# LB_BIT_o9_BARGRAPH-v02_rev1.net
KiCad netlist of a schematic drawn in EAGLE
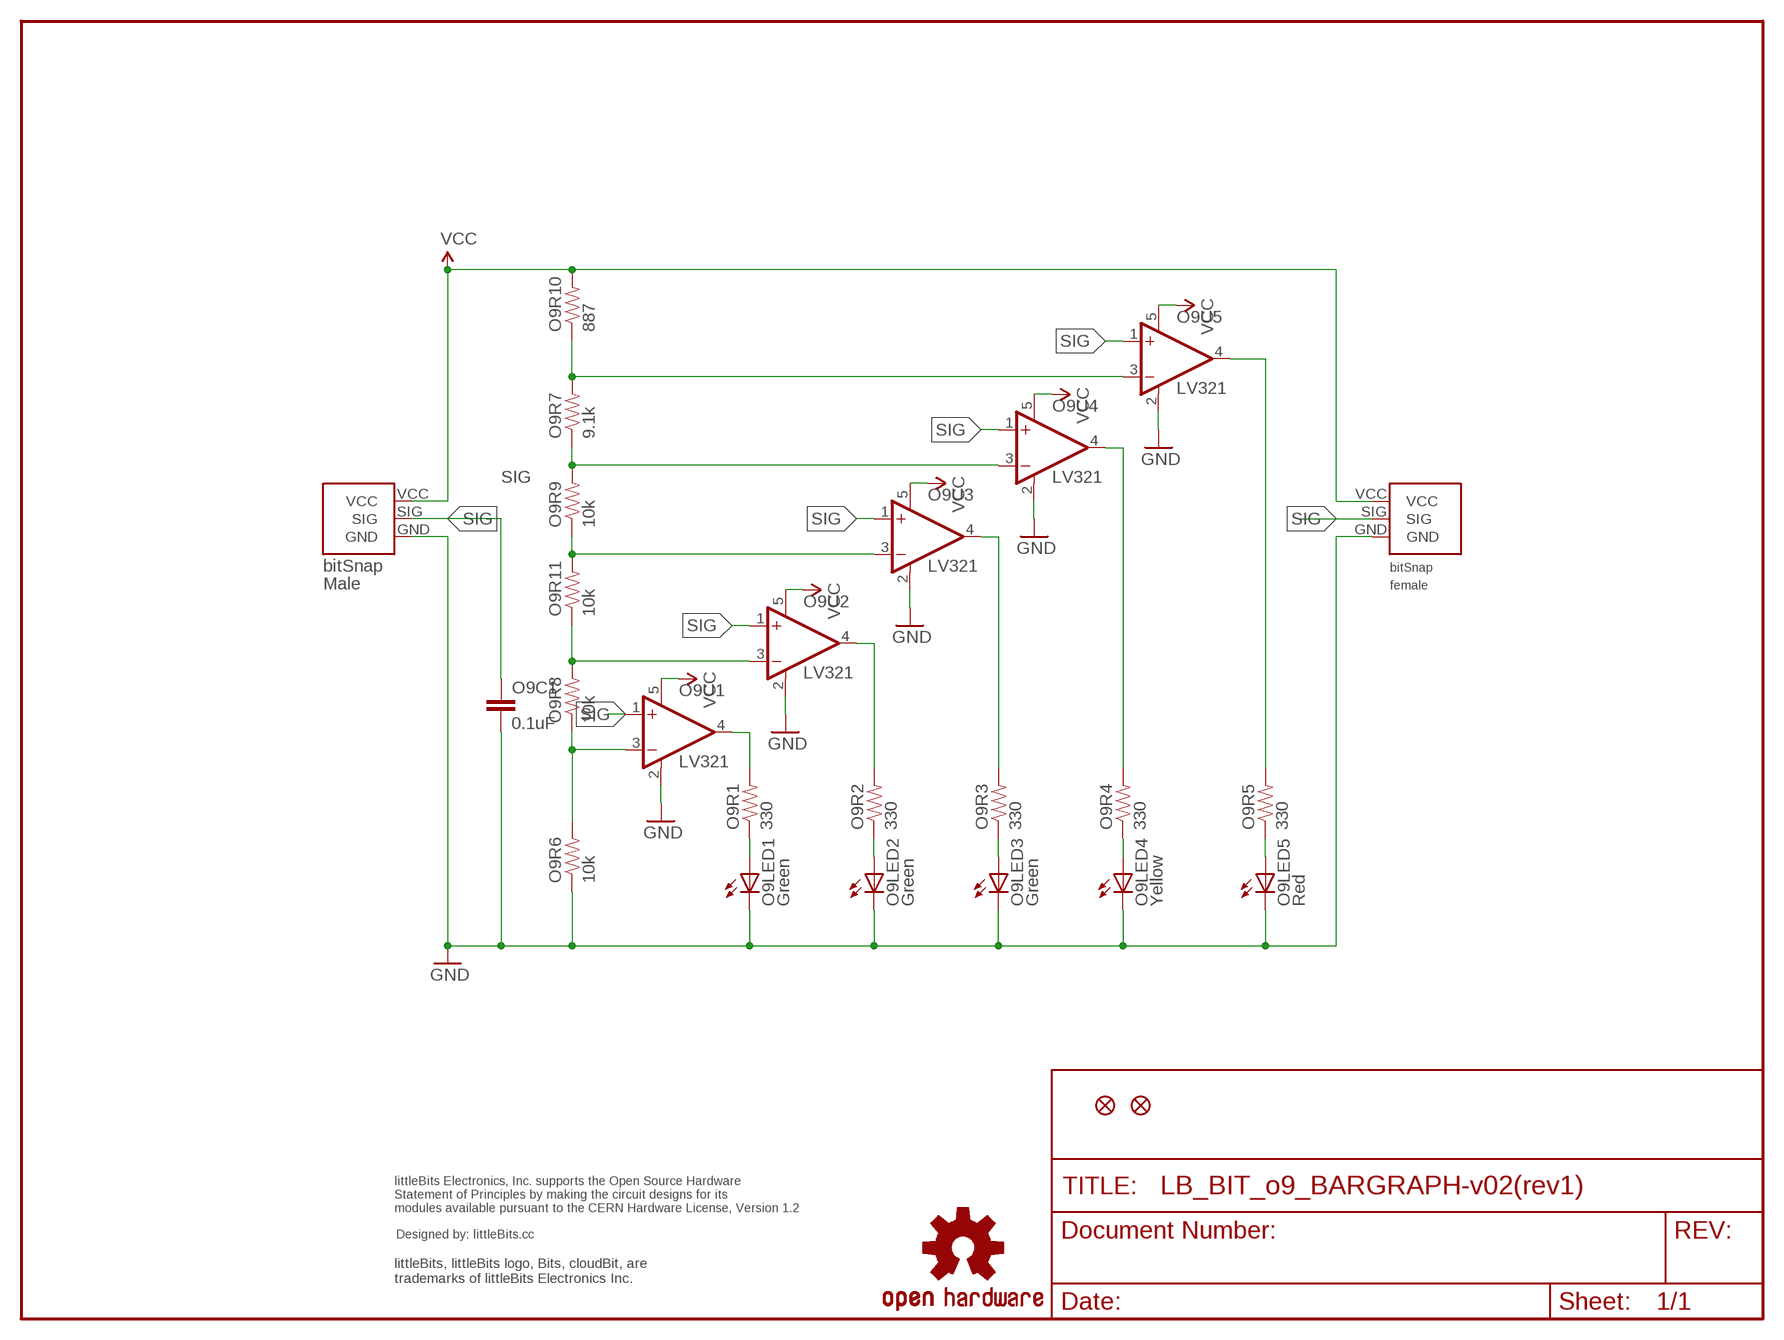
[diagram p0: schematic, sheet 1]

(export (version "E")
  (design (tool "Eeschema 10.0.6"))
  (components
    (comp (ref "JP1")
      (value "FIDUCIAL1X2.5")
      (footprint "eagle-import:FIDUCIAL-1X2.5")
      (libsource (lib "eagle-import") (part "FIDUCIAL1X2.5"))
    )
    (comp (ref "JP2")
      (value "FIDUCIAL1X2.5")
      (footprint "eagle-import:FIDUCIAL-1X2.5")
      (libsource (lib "eagle-import") (part "FIDUCIAL1X2.5"))
    )
    (comp (ref "O9BSF")
      (value "BITSNAP_FEMALE")
      (footprint "eagle-import:BITSNAP_FEMALE")
      (libsource (lib "eagle-import") (part "BITSNAP_FEMALE"))
    )
    (comp (ref "O9BSM")
      (value "BITSNAP_MALE")
      (footprint "eagle-import:BITSNAP_MALE")
      (libsource (lib "eagle-import") (part "BITSNAP_MALE"))
    )
    (comp (ref "O9C1")
      (value "0.1uF")
      (footprint "eagle-import:0603-CAP")
      (libsource (lib "eagle-import") (part "CAP0603-CAP"))
    )
    (comp (ref "O9LED1")
      (value "Green")
      (footprint "eagle-import:LED-1206")
      (libsource (lib "eagle-import") (part "LED1206"))
    )
    (comp (ref "O9LED2")
      (value "Green")
      (footprint "eagle-import:LED-1206")
      (libsource (lib "eagle-import") (part "LED1206"))
    )
    (comp (ref "O9LED3")
      (value "Green")
      (footprint "eagle-import:LED-1206")
      (libsource (lib "eagle-import") (part "LED1206"))
    )
    (comp (ref "O9LED4")
      (value "Yellow")
      (footprint "eagle-import:LED-1206")
      (libsource (lib "eagle-import") (part "LED1206"))
    )
    (comp (ref "O9LED5")
      (value "Red")
      (footprint "eagle-import:LED-1206")
      (libsource (lib "eagle-import") (part "LED1206"))
    )
    (comp (ref "O9R1")
      (value "330")
      (footprint "eagle-import:0603-RES")
      (libsource (lib "eagle-import") (part "RESISTOR0603-RES"))
    )
    (comp (ref "O9R2")
      (value "330")
      (footprint "eagle-import:0603-RES")
      (libsource (lib "eagle-import") (part "RESISTOR0603-RES"))
    )
    (comp (ref "O9R3")
      (value "330")
      (footprint "eagle-import:0603-RES")
      (libsource (lib "eagle-import") (part "RESISTOR0603-RES"))
    )
    (comp (ref "O9R4")
      (value "330")
      (footprint "eagle-import:0603-RES")
      (libsource (lib "eagle-import") (part "RESISTOR0603-RES"))
    )
    (comp (ref "O9R5")
      (value "330")
      (footprint "eagle-import:0603-RES")
      (libsource (lib "eagle-import") (part "RESISTOR0603-RES"))
    )
    (comp (ref "O9R6")
      (value "10k")
      (footprint "eagle-import:0603-RES")
      (libsource (lib "eagle-import") (part "RESISTOR0603-RES"))
    )
    (comp (ref "O9R7")
      (value "9.1k")
      (footprint "eagle-import:0603-RES")
      (libsource (lib "eagle-import") (part "RESISTOR0603-RES"))
    )
    (comp (ref "O9R8")
      (value "10k")
      (footprint "eagle-import:0603-RES")
      (libsource (lib "eagle-import") (part "RESISTOR0603-RES"))
    )
    (comp (ref "O9R9")
      (value "10k")
      (footprint "eagle-import:0603-RES")
      (libsource (lib "eagle-import") (part "RESISTOR0603-RES"))
    )
    (comp (ref "O9R10")
      (value "887")
      (footprint "eagle-import:0603-RES")
      (libsource (lib "eagle-import") (part "RESISTOR0603-RES"))
    )
    (comp (ref "O9R11")
      (value "10k")
      (footprint "eagle-import:0603-RES")
      (libsource (lib "eagle-import") (part "RESISTOR0603-RES"))
    )
    (comp (ref "O9U1")
      (value "LV321")
      (footprint "eagle-import:SC70-5")
      (libsource (lib "eagle-import") (part "LV321"))
    )
    (comp (ref "O9U2")
      (value "LV321")
      (footprint "eagle-import:SC70-5")
      (libsource (lib "eagle-import") (part "LV321"))
    )
    (comp (ref "O9U3")
      (value "LV321")
      (footprint "eagle-import:SC70-5")
      (libsource (lib "eagle-import") (part "LV321"))
    )
    (comp (ref "O9U4")
      (value "LV321")
      (footprint "eagle-import:SC70-5")
      (libsource (lib "eagle-import") (part "LV321"))
    )
    (comp (ref "O9U5")
      (value "LV321")
      (footprint "eagle-import:SC70-5")
      (libsource (lib "eagle-import") (part "LV321"))
    )
    (comp (ref "U$1")
      (value "OSHWCREDIT")
      (footprint "eagle-import:OSHWCREDIT")
      (libsource (lib "eagle-import") (part "OSHWCREDIT"))
    )
    (comp (ref "U$3")
      (value "OSHW-LOGOL")
      (footprint "eagle-import:OSHW-LOGO-L")
      (libsource (lib "eagle-import") (part "OSHW-LOGOL"))
    )
  )
  (nets
    (net (code "1") (name "GND") (class "Default")
      (node (ref "O9BSF") (pin "GND") (pinfunction "GND_GND") (pintype "bidirectional"))
      (node (ref "O9BSM") (pin "GND") (pinfunction "GND_GND") (pintype "bidirectional"))
      (node (ref "O9C1") (pin "2") (pinfunction "2_2") (pintype "passive"))
      (node (ref "O9LED1") (pin "C") (pinfunction "C_C") (pintype "passive"))
      (node (ref "O9LED2") (pin "C") (pinfunction "C_C") (pintype "passive"))
      (node (ref "O9LED3") (pin "C") (pinfunction "C_C") (pintype "passive"))
      (node (ref "O9LED4") (pin "C") (pinfunction "C_C") (pintype "passive"))
      (node (ref "O9LED5") (pin "C") (pinfunction "C_C") (pintype "passive"))
      (node (ref "O9R6") (pin "1") (pinfunction "1_1") (pintype "passive"))
      (node (ref "O9U1") (pin "2") (pinfunction "V-_2") (pintype "power_in"))
      (node (ref "O9U2") (pin "2") (pinfunction "V-_2") (pintype "power_in"))
      (node (ref "O9U3") (pin "2") (pinfunction "V-_2") (pintype "power_in"))
      (node (ref "O9U4") (pin "2") (pinfunction "V-_2") (pintype "power_in"))
      (node (ref "O9U5") (pin "2") (pinfunction "V-_2") (pintype "power_in"))
    )
    (net (code "2") (name "Net-(O9LED1-PadA)") (class "Default")
      (node (ref "O9LED1") (pin "A") (pinfunction "A_A") (pintype "passive"))
      (node (ref "O9R1") (pin "1") (pinfunction "1_1") (pintype "passive"))
    )
    (net (code "3") (name "Net-(O9LED2-PadA)") (class "Default")
      (node (ref "O9LED2") (pin "A") (pinfunction "A_A") (pintype "passive"))
      (node (ref "O9R2") (pin "1") (pinfunction "1_1") (pintype "passive"))
    )
    (net (code "4") (name "Net-(O9LED3-PadA)") (class "Default")
      (node (ref "O9LED3") (pin "A") (pinfunction "A_A") (pintype "passive"))
      (node (ref "O9R3") (pin "1") (pinfunction "1_1") (pintype "passive"))
    )
    (net (code "5") (name "Net-(O9LED4-PadA)") (class "Default")
      (node (ref "O9LED4") (pin "A") (pinfunction "A_A") (pintype "passive"))
      (node (ref "O9R4") (pin "1") (pinfunction "1_1") (pintype "passive"))
    )
    (net (code "6") (name "Net-(O9LED5-PadA)") (class "Default")
      (node (ref "O9LED5") (pin "A") (pinfunction "A_A") (pintype "passive"))
      (node (ref "O9R5") (pin "1") (pinfunction "1_1") (pintype "passive"))
    )
    (net (code "7") (name "Net-(O9U1--IN)") (class "Default")
      (node (ref "O9R6") (pin "2") (pinfunction "2_2") (pintype "passive"))
      (node (ref "O9R8") (pin "1") (pinfunction "1_1") (pintype "passive"))
      (node (ref "O9U1") (pin "3") (pinfunction "-IN_3") (pintype "input"))
    )
    (net (code "8") (name "Net-(O9U1-OUT)") (class "Default")
      (node (ref "O9R1") (pin "2") (pinfunction "2_2") (pintype "passive"))
      (node (ref "O9U1") (pin "4") (pinfunction "OUT_4") (pintype "output"))
    )
    (net (code "9") (name "Net-(O9U2--IN)") (class "Default")
      (node (ref "O9R11") (pin "1") (pinfunction "1_1") (pintype "passive"))
      (node (ref "O9R8") (pin "2") (pinfunction "2_2") (pintype "passive"))
      (node (ref "O9U2") (pin "3") (pinfunction "-IN_3") (pintype "input"))
    )
    (net (code "10") (name "Net-(O9U2-OUT)") (class "Default")
      (node (ref "O9R2") (pin "2") (pinfunction "2_2") (pintype "passive"))
      (node (ref "O9U2") (pin "4") (pinfunction "OUT_4") (pintype "output"))
    )
    (net (code "11") (name "Net-(O9U3--IN)") (class "Default")
      (node (ref "O9R11") (pin "2") (pinfunction "2_2") (pintype "passive"))
      (node (ref "O9R9") (pin "1") (pinfunction "1_1") (pintype "passive"))
      (node (ref "O9U3") (pin "3") (pinfunction "-IN_3") (pintype "input"))
    )
    (net (code "12") (name "Net-(O9U3-OUT)") (class "Default")
      (node (ref "O9R3") (pin "2") (pinfunction "2_2") (pintype "passive"))
      (node (ref "O9U3") (pin "4") (pinfunction "OUT_4") (pintype "output"))
    )
    (net (code "13") (name "Net-(O9U4--IN)") (class "Default")
      (node (ref "O9R7") (pin "1") (pinfunction "1_1") (pintype "passive"))
      (node (ref "O9R9") (pin "2") (pinfunction "2_2") (pintype "passive"))
      (node (ref "O9U4") (pin "3") (pinfunction "-IN_3") (pintype "input"))
    )
    (net (code "14") (name "Net-(O9U4-OUT)") (class "Default")
      (node (ref "O9R4") (pin "2") (pinfunction "2_2") (pintype "passive"))
      (node (ref "O9U4") (pin "4") (pinfunction "OUT_4") (pintype "output"))
    )
    (net (code "15") (name "Net-(O9U5--IN)") (class "Default")
      (node (ref "O9R10") (pin "1") (pinfunction "1_1") (pintype "passive"))
      (node (ref "O9R7") (pin "2") (pinfunction "2_2") (pintype "passive"))
      (node (ref "O9U5") (pin "3") (pinfunction "-IN_3") (pintype "input"))
    )
    (net (code "16") (name "Net-(O9U5-OUT)") (class "Default")
      (node (ref "O9R5") (pin "2") (pinfunction "2_2") (pintype "passive"))
      (node (ref "O9U5") (pin "4") (pinfunction "OUT_4") (pintype "output"))
    )
    (net (code "17") (name "SIG") (class "Default")
      (node (ref "O9BSF") (pin "SIG") (pinfunction "SIG_SIG") (pintype "bidirectional"))
      (node (ref "O9BSM") (pin "SIG") (pinfunction "SIG_SIG") (pintype "bidirectional"))
      (node (ref "O9C1") (pin "1") (pinfunction "1_1") (pintype "passive"))
      (node (ref "O9U1") (pin "1") (pinfunction "+IN_1") (pintype "input"))
      (node (ref "O9U2") (pin "1") (pinfunction "+IN_1") (pintype "input"))
      (node (ref "O9U3") (pin "1") (pinfunction "+IN_1") (pintype "input"))
      (node (ref "O9U4") (pin "1") (pinfunction "+IN_1") (pintype "input"))
      (node (ref "O9U5") (pin "1") (pinfunction "+IN_1") (pintype "input"))
    )
    (net (code "18") (name "VCC") (class "Default")
      (node (ref "O9BSF") (pin "VCC") (pinfunction "VCC_VCC") (pintype "bidirectional"))
      (node (ref "O9BSM") (pin "VCC") (pinfunction "VCC_VCC") (pintype "bidirectional"))
      (node (ref "O9R10") (pin "2") (pinfunction "2_2") (pintype "passive"))
      (node (ref "O9U1") (pin "5") (pinfunction "V+_5") (pintype "power_in"))
      (node (ref "O9U2") (pin "5") (pinfunction "V+_5") (pintype "power_in"))
      (node (ref "O9U3") (pin "5") (pinfunction "V+_5") (pintype "power_in"))
      (node (ref "O9U4") (pin "5") (pinfunction "V+_5") (pintype "power_in"))
      (node (ref "O9U5") (pin "5") (pinfunction "V+_5") (pintype "power_in"))
    )
  )
)
